# Driver_Modulation.net
KiCad netlist of a schematic drawn in Altium Designer
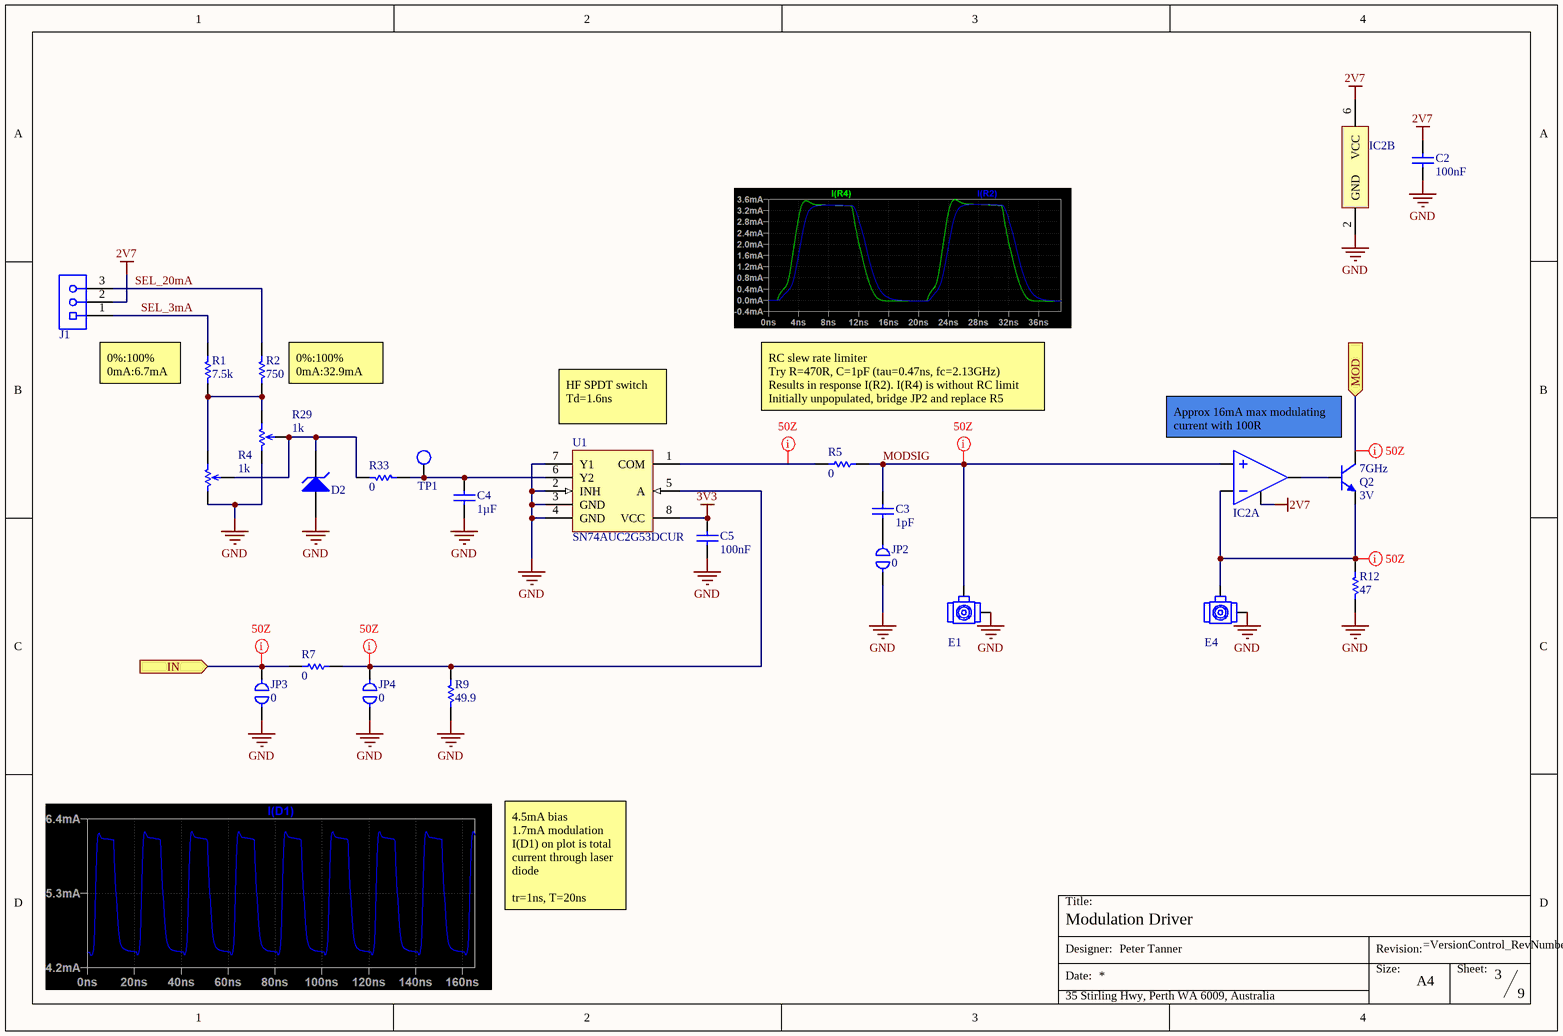
[diagram p0: Driver_Modulation.SchDoc]

(export (version "E")
  (design (tool "Eeschema 10.0.6"))
  (components
    (comp (ref "C2")
      (value "100nF")
      (footprint "CAPC1005X06N")
      (fields (field (name "TOLERANCE") "10%") (field (name "Comment") "CL05B104KB54PNC"))
      (libsource (lib "UWA Aerospace") (part "Capacitor - Non-polar"))
    )
    (comp (ref "C3")
      (value "1pF")
      (footprint "CAPC1005X06N")
      (description "Cap Ceramic 1pF 50V C0G 5% Pad SMD 0402 125C Automotive T/R")
      (fields (field (name "TOLERANCE") "5%") (field (name "Comment") "GCM1555C1H1R0JA16D"))
      (libsource (lib "UWA Aerospace") (part "Capacitor - Non-polar"))
    )
    (comp (ref "C4")
      (value "1µF")
      (footprint "CAPC1005X06N")
      (fields (field (name "TOLERANCE") "10%") (field (name "Comment") "CL05A105KA5NQNC"))
      (libsource (lib "UWA Aerospace") (part "Capacitor - Non-polar"))
    )
    (comp (ref "C5")
      (value "100nF")
      (footprint "CAPC1005X06N")
      (fields (field (name "TOLERANCE") "10%") (field (name "Comment") "CL05B104KB54PNC"))
      (libsource (lib "UWA Aerospace") (part "Capacitor - Non-polar"))
    )
    (comp (ref "D2")
      (value "H5VU10U")
      (footprint "DFN60P100X45-2L")
      (description "5A 55W 16V 9V Unidirectional 5V DFN1006-2L  ESD and Surge Protection (TVS/ESD) ROHS")
      (libsource (lib "UWA Aerospace") (part "Diode - Zener"))
    )
    (comp (ref "E1")
      (value "U.FL-R-SMT-1(01)")
      (footprint "HRS-U.FL-R-SMT-3_V 4_LAYER_KO")
      (description "Rf Connectors / Coaxial Connectors SMT Ml Rec Au 50 Ohm W/anti Sldr Wicking UFL")
      (fields (field (name "SOURCE") "UWAA_Stock"))
      (libsource (lib "UWA Aerospace") (part "U.FL Connector"))
    )
    (comp (ref "E4")
      (value "U.FL-R-SMT-1(01)")
      (footprint "HRS-U.FL-R-SMT-3_V 4_LAYER_KO")
      (description "Rf Connectors / Coaxial Connectors SMT Ml Rec Au 50 Ohm W/anti Sldr Wicking UFL")
      (fields (field (name "SOURCE") "UWAA_Stock"))
      (libsource (lib "UWA Aerospace") (part "U.FL Connector"))
    )
    (comp (ref "IC2")
      (value "OPA355NA/3K")
      (footprint "DBV0006A_SOT-23-6_TI__SOT95P280X145-6L")
      (description "Operational Amplifier, 1 Func, 9000uV Offset-Max, 100MHz Band Width, CMOS, PDSO6")
      (fields (field (name "SOURCE") "JLCPCB(Extended,Economic_PCBA)"))
      (libsource (lib "UWA Aerospace") (part "Amplifier - Operational w/ EN"))
    )
    (comp (ref "J1")
      (value "10129378-903001BLF")
      (footprint "10129378-903001BLF-Footprint-1")
      (description "Conn Unshrouded Header HDR 3 POS 2.54mm Solder ST Thru-Hole Poly Bag")
      (fields (field (name "SOURCE") "Aliexpress"))
      (libsource (lib "UWA Aerospace") (part "10129378-903001BLF"))
    )
    (comp (ref "JP2")
      (value "0")
      (footprint "JUMPER-0402-Footprint-1")
      (description "0402 pad placeholder for 0-ohm resistor jumper")
      (fields
        (field (name "TOLERANCE") "1%")
        (field (name "Comment") "JUMPER-0402")
        (field (name "SOURCE") "Distributor")
      )
      (libsource (lib "UWA Aerospace") (part "Jumper - Open"))
    )
    (comp (ref "JP3")
      (value "0")
      (footprint "RESC1005X04N")
      (description "0402 pad placeholder for 0-ohm resistor jumper")
      (fields
        (field (name "TOLERANCE") "1%")
        (field (name "Comment") "JUMPER-0402")
        (field (name "SOURCE") "Distributor")
      )
      (libsource (lib "UWA Aerospace") (part "Jumper - Open"))
    )
    (comp (ref "JP4")
      (value "0")
      (footprint "RESC1005X04N")
      (description "0402 pad placeholder for 0-ohm resistor jumper")
      (fields
        (field (name "TOLERANCE") "1%")
        (field (name "Comment") "JUMPER-0402")
        (field (name "SOURCE") "Distributor")
      )
      (libsource (lib "UWA Aerospace") (part "Jumper - Open"))
    )
    (comp (ref "Q2")
      (value "2SC3356")
      (footprint "SOT-23_hongjiacheng__SOT95P240X115-3L")
      (description "RF Small Signal Bipolar Transistor, 0.1A I(C), 1-Element, Ultra High Frequency Band, Silicon, NPN")
      (fields (field (name "FREQUENCY") "7GHz") (field (name "EMITTER BASE VOLTAGE (VEBO)") "3V"))
      (libsource (lib "UWA Aerospace") (part "Transistor - BJT NPN"))
    )
    (comp (ref "R1")
      (value "7.5k")
      (footprint "RESC2012X05N")
      (fields (field (name "TOLERANCE") "1%") (field (name "Comment") "0805W8F7501T5E"))
      (libsource (lib "UWA Aerospace") (part "Resistor"))
    )
    (comp (ref "R2")
      (value "750")
      (footprint "RESC2012X05N")
      (description "Thick Film Resistors - SMD RMC 0805 1/8W 1% T/R-5000")
      (fields (field (name "TOLERANCE") "1%") (field (name "Comment") "0805W8F7500T5E"))
      (libsource (lib "UWA Aerospace") (part "Resistor"))
    )
    (comp (ref "R4")
      (value "1k")
      (footprint "BOUR-TC33X-2_V")
      (description "SMD 3mm Cermet Trimmer - Leadfree 3MM 1KOHMS 25% 0.1WATT OPEN FRM")
      (fields (field (name "TOLERANCE") "25%") (field (name "Comment") "TC33X-2-102E"))
      (libsource (lib "UWA Aerospace") (part "Resistor - Adjustable"))
    )
    (comp (ref "R5")
      (value "0")
      (footprint "RESC1005X04N")
      (description "Metal Glaze/thick Film, 0.0625W, 0ohm, 0402")
      (fields (field (name "TOLERANCE") "1%") (field (name "Comment") "0402WGF0000TCE"))
      (libsource (lib "UWA Aerospace") (part "Resistor"))
    )
    (comp (ref "R7")
      (value "0")
      (footprint "RESC1005X04N")
      (description "Metal Glaze/thick Film, 0.0625W, 0ohm, 0402")
      (fields (field (name "TOLERANCE") "1%") (field (name "Comment") "0402WGF0000TCE"))
      (libsource (lib "UWA Aerospace") (part "Resistor"))
    )
    (comp (ref "R9")
      (value "49.9")
      (footprint "RESC1005X04N")
      (description "62.5mW Thick Film Resistors 50V ±100ppm/℃ ±1% 49.9Ω 0402 Chip Resistor - Surface Mount ROHS")
      (fields (field (name "TOLERANCE") "1%") (field (name "Comment") "0402WGF499JTCE"))
      (libsource (lib "UWA Aerospace") (part "Resistor"))
    )
    (comp (ref "R12")
      (value "47")
      (footprint "RESC1608X05N")
      (description "Res Thick Film 0603 47 Ohm 1% 0.1W(1/10W) ±100ppm/C Pad SMD T/R")
      (fields (field (name "TOLERANCE") "1%") (field (name "Comment") "RC0603FR-0747RL"))
      (libsource (lib "UWA Aerospace") (part "Resistor"))
    )
    (comp (ref "R29")
      (value "1k")
      (footprint "POT_RK0971-L-15KC_N-1")
      (description "Potentiometer, 0.05W, 1000ohm, 10V, 20% +/-Tol, 1 Turn(s)")
      (fields
        (field (name "TOLERANCE") "20%")
        (field (name "Comment") "RK097_1K")
        (field (name "SOURCE") "Aliexpress")
      )
      (libsource (lib "UWA Aerospace") (part "Resistor - Adjustable"))
    )
    (comp (ref "R33")
      (value "0")
      (footprint "RESC1005X04N")
      (description "Metal Glaze/thick Film, 0.0625W, 0ohm, 0402")
      (fields (field (name "TOLERANCE") "1%") (field (name "Comment") "0402WGF0000TCE"))
      (libsource (lib "UWA Aerospace") (part "Resistor"))
    )
    (comp (ref "TP1")
      (value "Test Point 5001")
      (footprint "FP-5001-MFG")
      (fields (field (name "SOURCE") "UWAA_Stock"))
      (libsource (lib "UWA Aerospace") (part "Test Point"))
    )
    (comp (ref "U1")
      (value "SN74AUC2G53DCUR")
      (footprint "DCU0008A_N")
      (description "2.5-V, 2: 1 (SPDT), 1-channel general-purpose analog switch 8-VSSOP -40 to 85")
      (fields (field (name "SOURCE") "Distributor"))
      (libsource (lib "UWA Aerospace") (part "TI-SN74XXX2G53-8"))
    )
  )
  (nets
    (net (code "1") (name "/IN") (class "Default")
      (node (ref "JP3") (pin "2") (pinfunction "2_2") (pintype "passive"))
      (node (ref "R7") (pin "2") (pinfunction "2_2") (pintype "passive"))
    )
    (net (code "2") (name "/MOD") (class "Default")
      (node (ref "Q2") (pin "1") (pinfunction "C_1") (pintype "passive"))
    )
    (net (code "3") (name "/MODSIG") (class "Default")
      (node (ref "C3") (pin "2") (pinfunction "2_2") (pintype "passive"))
      (node (ref "E1") (pin "1") (pinfunction "SIG_1") (pintype "passive"))
      (node (ref "IC2") (pin "3") (pinfunction "VIN+_3") (pintype "passive"))
      (node (ref "R5") (pin "1") (pinfunction "1_1") (pintype "passive"))
    )
    (net (code "4") (name "/SEL_3mA") (class "Default")
      (node (ref "J1") (pin "1") (pinfunction "1_1") (pintype "passive"))
      (node (ref "R1") (pin "2") (pinfunction "2_2") (pintype "passive"))
    )
    (net (code "5") (name "/SEL_20mA") (class "Default")
      (node (ref "J1") (pin "3") (pinfunction "3_3") (pintype "passive"))
      (node (ref "R2") (pin "2") (pinfunction "2_2") (pintype "passive"))
    )
    (net (code "6") (name "2V7") (class "Default")
      (node (ref "C2") (pin "2") (pinfunction "2_2") (pintype "passive"))
      (node (ref "IC2") (pin "5") (pinfunction "ENABLE_5") (pintype "passive"))
      (node (ref "IC2") (pin "6") (pinfunction "VCC_6") (pintype "passive"))
      (node (ref "J1") (pin "2") (pinfunction "2_2") (pintype "passive"))
    )
    (net (code "7") (name "3V3") (class "Default")
      (node (ref "C5") (pin "2") (pinfunction "2_2") (pintype "passive"))
      (node (ref "U1") (pin "8") (pinfunction "VCC_8") (pintype "power_in"))
    )
    (net (code "8") (name "GND") (class "Default")
      (node (ref "C2") (pin "1") (pinfunction "1_1") (pintype "passive"))
      (node (ref "C4") (pin "1") (pinfunction "1_1") (pintype "passive"))
      (node (ref "C5") (pin "1") (pinfunction "1_1") (pintype "passive"))
      (node (ref "D2") (pin "2") (pinfunction "A_2") (pintype "passive"))
      (node (ref "E1") (pin "2") (pinfunction "GND_2") (pintype "passive"))
      (node (ref "E4") (pin "2") (pinfunction "GND_2") (pintype "passive"))
      (node (ref "IC2") (pin "2") (pinfunction "GND_2") (pintype "passive"))
      (node (ref "JP2") (pin "1") (pinfunction "1_1") (pintype "passive"))
      (node (ref "JP3") (pin "1") (pinfunction "1_1") (pintype "passive"))
      (node (ref "JP4") (pin "1") (pinfunction "1_1") (pintype "passive"))
      (node (ref "R12") (pin "1") (pinfunction "1_1") (pintype "passive"))
      (node (ref "R29") (pin "1") (pinfunction "CCW_1") (pintype "passive"))
      (node (ref "R4") (pin "1") (pinfunction "CCW_1") (pintype "passive"))
      (node (ref "R9") (pin "1") (pinfunction "1_1") (pintype "passive"))
      (node (ref "U1") (pin "2") (pinfunction "INH_2") (pintype "input"))
      (node (ref "U1") (pin "3") (pinfunction "GND_3") (pintype "power_in"))
      (node (ref "U1") (pin "4") (pinfunction "GND_4") (pintype "power_in"))
      (node (ref "U1") (pin "7") (pinfunction "Y1_7") (pintype "passive"))
    )
    (net (code "9") (name "Net-(C3-Pad1)") (class "Default")
      (node (ref "C3") (pin "1") (pinfunction "1_1") (pintype "passive"))
      (node (ref "JP2") (pin "2") (pinfunction "2_2") (pintype "passive"))
    )
    (net (code "10") (name "Net-(D2-K)") (class "Default")
      (node (ref "D2") (pin "1") (pinfunction "K_1") (pintype "passive"))
      (node (ref "R29") (pin "2") (pinfunction "W_2") (pintype "passive"))
      (node (ref "R33") (pin "2") (pinfunction "2_2") (pintype "passive"))
      (node (ref "R4") (pin "2") (pinfunction "W_2") (pintype "passive"))
    )
    (net (code "11") (name "Net-(E4-SIG)") (class "Default")
      (node (ref "E4") (pin "1") (pinfunction "SIG_1") (pintype "passive"))
      (node (ref "IC2") (pin "4") (pinfunction "VIN-_4") (pintype "passive"))
      (node (ref "Q2") (pin "3") (pinfunction "E_3") (pintype "passive"))
      (node (ref "R12") (pin "2") (pinfunction "2_2") (pintype "passive"))
    )
    (net (code "12") (name "Net-(IC2A-VOUT)") (class "Default")
      (node (ref "IC2") (pin "1") (pinfunction "VOUT_1") (pintype "passive"))
      (node (ref "Q2") (pin "2") (pinfunction "B_2") (pintype "passive"))
    )
    (net (code "13") (name "Net-(R29-CW)") (class "Default")
      (node (ref "R1") (pin "1") (pinfunction "1_1") (pintype "passive"))
      (node (ref "R2") (pin "1") (pinfunction "1_1") (pintype "passive"))
      (node (ref "R29") (pin "3") (pinfunction "CW_3") (pintype "passive"))
      (node (ref "R4") (pin "3") (pinfunction "CW_3") (pintype "passive"))
    )
    (net (code "14") (name "Net-(U1-A)") (class "Default")
      (node (ref "JP4") (pin "2") (pinfunction "2_2") (pintype "passive"))
      (node (ref "R7") (pin "1") (pinfunction "1_1") (pintype "passive"))
      (node (ref "R9") (pin "2") (pinfunction "2_2") (pintype "passive"))
      (node (ref "U1") (pin "5") (pinfunction "A_5") (pintype "input"))
    )
    (net (code "15") (name "Net-(U1-COM)") (class "Default")
      (node (ref "R5") (pin "2") (pinfunction "2_2") (pintype "passive"))
      (node (ref "U1") (pin "1") (pinfunction "COM_1") (pintype "passive"))
    )
    (net (code "16") (name "Net-(U1-Y2)") (class "Default")
      (node (ref "C4") (pin "2") (pinfunction "2_2") (pintype "passive"))
      (node (ref "R33") (pin "1") (pinfunction "1_1") (pintype "passive"))
      (node (ref "TP1") (pin "1") (pinfunction "1_1") (pintype "passive"))
      (node (ref "U1") (pin "6") (pinfunction "Y2_6") (pintype "passive"))
    )
  )
)
